# PowerSupply.net
KiCad netlist of a schematic drawn in Altium Designer
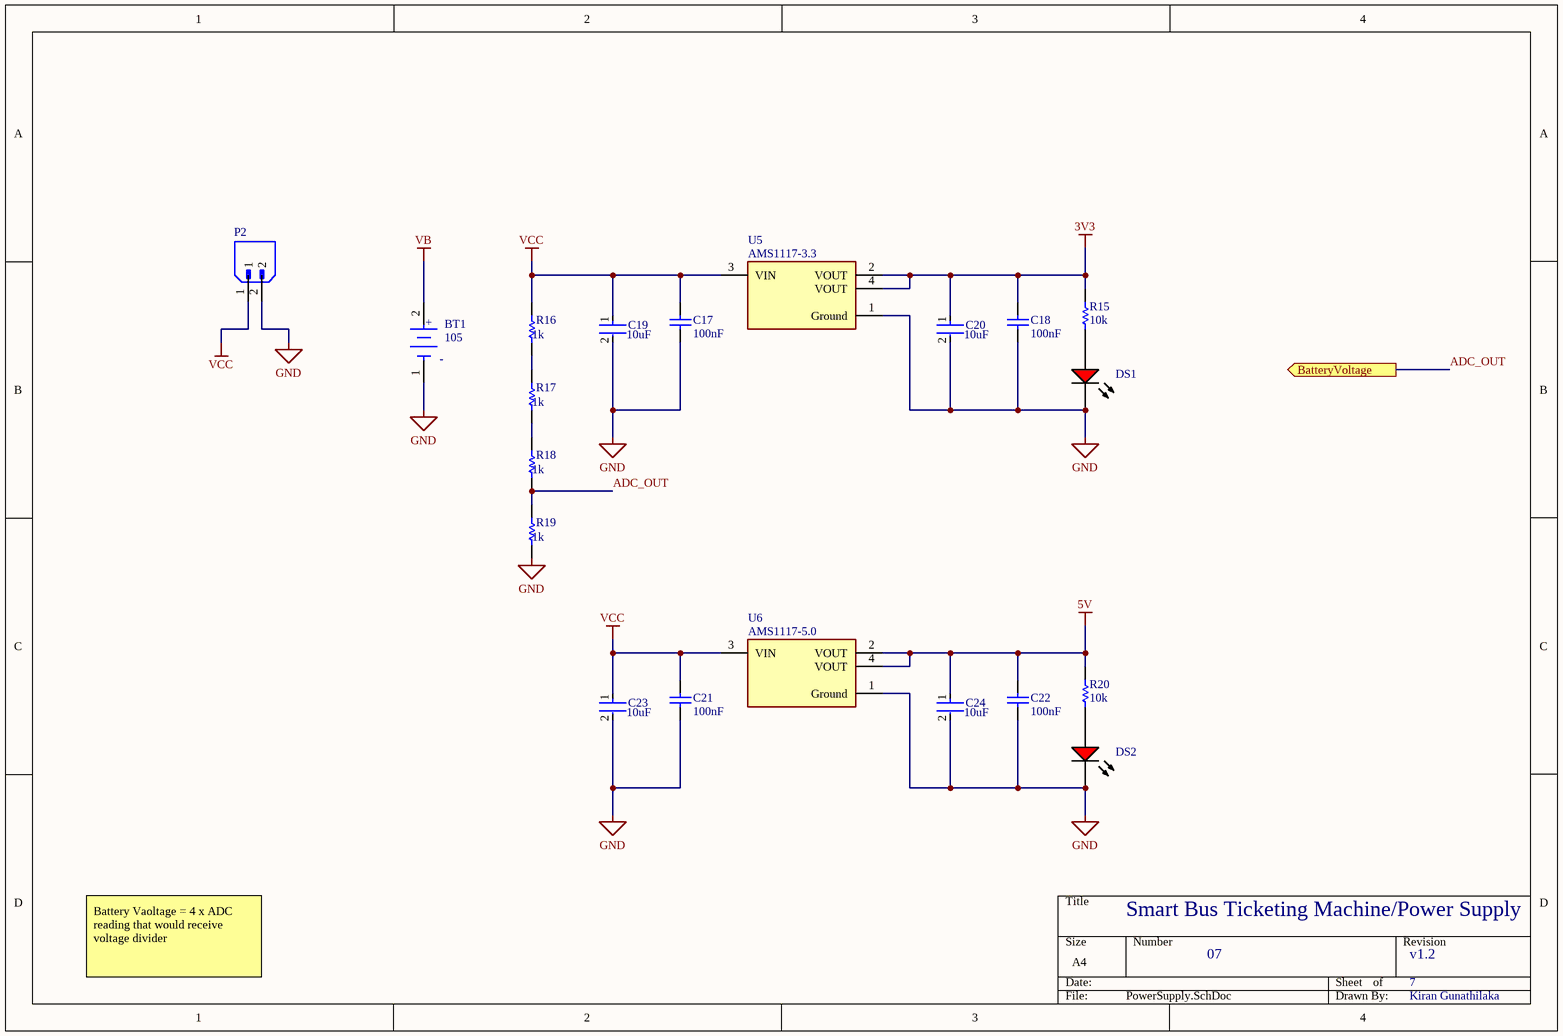
[diagram p0: PowerSupply.SchDoc]

(export (version "E")
  (design (tool "Eeschema 10.0.6"))
  (components
    (comp (ref "BT1")
      (value "105")
      (footprint "FP-105-MFG")
      (description "105 Battery Holder Coin Cell 1 Cell PC Pin PCB Through Hole Mount PBT 0.944 in. Dia")
      (libsource (lib "Altium Content Vault") (part "db879b5662d49c975a5ff8b5862d222"))
    )
    (comp (ref "C17")
      (value "100nF")
      (footprint "CAPC2013X94X50ML20T25")
      (fields
        (field (name "MANUFACTURER") "AVX Interconnect / Elco")
        (field (name "PART NUMBER") "08051C152KAT2A")
      )
      (libsource (lib "Altium Content Vault") (part "CAP"))
    )
    (comp (ref "C18")
      (value "100nF")
      (footprint "CAPC2013X94X50ML20T25")
      (fields
        (field (name "MANUFACTURER") "AVX Interconnect / Elco")
        (field (name "PART NUMBER") "08051C152KAT2A")
      )
      (libsource (lib "Altium Content Vault") (part "CAP"))
    )
    (comp (ref "C19")
      (value "C0805C106K9PACTU")
      (footprint "FP-C0805C106K9PACTU-MFG")
      (description "CAP CER 10UF 6.3V X5R 0805")
      (fields
        (field (name "CAPACITANCE") "10uF")
        (field (name "VOLTAGE") "6.3V")
        (field (name "TOLERANCE") "10%")
      )
      (libsource (lib "Altium Content Vault") (part "b4654b650e69147ec39a6b967a45e02"))
    )
    (comp (ref "C20")
      (value "C0805C106K9PACTU")
      (footprint "FP-C0805C106K9PACTU-MFG")
      (description "CAP CER 10UF 6.3V X5R 0805")
      (fields
        (field (name "CAPACITANCE") "10uF")
        (field (name "VOLTAGE") "6.3V")
        (field (name "TOLERANCE") "10%")
      )
      (libsource (lib "Altium Content Vault") (part "b4654b650e69147ec39a6b967a45e02"))
    )
    (comp (ref "C21")
      (value "100nF")
      (footprint "CAPC2013X94X50ML20T25")
      (fields
        (field (name "MANUFACTURER") "AVX Interconnect / Elco")
        (field (name "PART NUMBER") "08051C152KAT2A")
      )
      (libsource (lib "Altium Content Vault") (part "CAP"))
    )
    (comp (ref "C22")
      (value "100nF")
      (footprint "CAPC2013X94X50ML20T25")
      (fields
        (field (name "MANUFACTURER") "AVX Interconnect / Elco")
        (field (name "PART NUMBER") "08051C152KAT2A")
      )
      (libsource (lib "Altium Content Vault") (part "CAP"))
    )
    (comp (ref "C23")
      (value "C0805C106K9PACTU")
      (footprint "FP-C0805C106K9PACTU-MFG")
      (description "CAP CER 10UF 6.3V X5R 0805")
      (fields
        (field (name "CAPACITANCE") "10uF")
        (field (name "VOLTAGE") "6.3V")
        (field (name "TOLERANCE") "10%")
      )
      (libsource (lib "Altium Content Vault") (part "b4654b650e69147ec39a6b967a45e02"))
    )
    (comp (ref "C24")
      (value "C0805C106K9PACTU")
      (footprint "FP-C0805C106K9PACTU-MFG")
      (description "CAP CER 10UF 6.3V X5R 0805")
      (fields
        (field (name "CAPACITANCE") "10uF")
        (field (name "VOLTAGE") "6.3V")
        (field (name "TOLERANCE") "10%")
      )
      (libsource (lib "Altium Content Vault") (part "b4654b650e69147ec39a6b967a45e02"))
    )
    (comp (ref "DS1")
      (value "HSMH-C150")
      (footprint "AVAG-HSMX-C150_V")
      (description "LED Uni-Color Red, 65 mW, 25 mA, -40 to 85 degC, 2-Pin SMD, RoHS, Tape and Reel")
      (fields (field (name "MANUFACTURER") "Avago"))
      (libsource (lib "Altium Content Vault") (part "LED-RED-AK-2"))
    )
    (comp (ref "DS2")
      (value "HSMH-C150")
      (footprint "AVAG-HSMX-C150_V")
      (description "LED Uni-Color Red, 65 mW, 25 mA, -40 to 85 degC, 2-Pin SMD, RoHS, Tape and Reel")
      (fields (field (name "MANUFACTURER") "Avago"))
      (libsource (lib "Altium Content Vault") (part "LED-RED-AK-2"))
    )
    (comp (ref "P2")
      (value "Battery Connector")
      (footprint "JST_B2B-XH-A(LF)(SN)")
      (libsource (lib "SchemLib") (part "TX_RX Header"))
    )
    (comp (ref "R15")
      (value "10k")
      (footprint "RESC2013X60X35NL10T20")
      (description "Chip Resistor, 10 KOhm, +/- 1%, 0.125 W, -55 to 155 degC, 0805 (2012 Metric), RoHS, Tape and Reel")
      (fields (field (name "MANUFACTURER") "Yageo") (field (name "Comment") "RC0805FR-0710KL"))
      (libsource (lib "Altium Content Vault") (part "RES-2"))
    )
    (comp (ref "R16")
      (value "RC0805FR-071KL")
      (footprint "RESC2013X60X35ML10T20")
      (description "Chip Resistor, 1 KOhm, +/- 1%, 125 mW, -55 to 155 degC, 0805 (2012 Metric), RoHS, Tape and Reel")
      (fields
        (field (name "RESISTANCE") "1k")
        (field (name "TOLERANCE") "1%")
        (field (name "MANUFACTURER") "Yageo")
      )
      (libsource (lib "Altium Content Vault") (part "RES-2"))
    )
    (comp (ref "R17")
      (value "RC0805FR-071KL")
      (footprint "RESC2013X60X35ML10T20")
      (description "Chip Resistor, 1 KOhm, +/- 1%, 125 mW, -55 to 155 degC, 0805 (2012 Metric), RoHS, Tape and Reel")
      (fields
        (field (name "RESISTANCE") "1k")
        (field (name "TOLERANCE") "1%")
        (field (name "MANUFACTURER") "Yageo")
      )
      (libsource (lib "Altium Content Vault") (part "RES-2"))
    )
    (comp (ref "R18")
      (value "RC0805FR-071KL")
      (footprint "RESC2013X60X35ML10T20")
      (description "Chip Resistor, 1 KOhm, +/- 1%, 125 mW, -55 to 155 degC, 0805 (2012 Metric), RoHS, Tape and Reel")
      (fields
        (field (name "RESISTANCE") "1k")
        (field (name "TOLERANCE") "1%")
        (field (name "MANUFACTURER") "Yageo")
      )
      (libsource (lib "Altium Content Vault") (part "RES-2"))
    )
    (comp (ref "R19")
      (value "RC0805FR-071KL")
      (footprint "RESC2013X60X35ML10T20")
      (description "Chip Resistor, 1 KOhm, +/- 1%, 125 mW, -55 to 155 degC, 0805 (2012 Metric), RoHS, Tape and Reel")
      (fields
        (field (name "RESISTANCE") "1k")
        (field (name "TOLERANCE") "1%")
        (field (name "MANUFACTURER") "Yageo")
      )
      (libsource (lib "Altium Content Vault") (part "RES-2"))
    )
    (comp (ref "R20")
      (value "10k")
      (footprint "RESC2013X60X35NL10T20")
      (description "Chip Resistor, 10 KOhm, +/- 1%, 0.125 W, -55 to 155 degC, 0805 (2012 Metric), RoHS, Tape and Reel")
      (fields (field (name "MANUFACTURER") "Yageo") (field (name "Comment") "RC0805FR-0710KL"))
      (libsource (lib "Altium Content Vault") (part "RES-2"))
    )
    (comp (ref "U5")
      (value "AMS1117-3.3")
      (footprint "FP-AMS1117-IPC_C")
      (description "LDO Voltage Regulators 1A, 3.3V")
      (fields
        (field (name "OCTOPART") "https://octopart.com/ams1117-3.3-advanced+monolithic+systems-25899300")
        (field (name "MANUFACTURER") "Advanced Monolithic Systems")
      )
      (libsource (lib "Altium Content Vault") (part "8bdbb5f8e77002000e30dd2845d0354"))
    )
    (comp (ref "U6")
      (value "AMS1117-5.0")
      (footprint "FP-AMS1117-IPC_C")
      (description "LDO Voltage Regulators 1A, 3.3V")
      (fields
        (field (name "MANUFACTURER PART NUMBER") "AMS1117-3.3")
        (field (name "OCTOPART") "https://octopart.com/ams1117-3.3-advanced+monolithic+systems-25899300")
      )
      (libsource (lib "Altium Content Vault") (part "8bdbb5f8e77002000e30dd2845d0354"))
    )
  )
  (nets
    (net (code "1") (name "/ADC_OUT") (class "Default")
      (node (ref "R18") (pin "1") (pinfunction "1_1") (pintype "passive"))
      (node (ref "R19") (pin "2") (pinfunction "2_2") (pintype "passive"))
    )
    (net (code "2") (name "3V3") (class "Default")
      (node (ref "C18") (pin "2") (pinfunction "2_2") (pintype "passive"))
      (node (ref "C20") (pin "1") (pinfunction "1_1") (pintype "passive"))
      (node (ref "R15") (pin "1") (pinfunction "1_1") (pintype "passive"))
      (node (ref "U5") (pin "2") (pinfunction "VOUT_2") (pintype "passive"))
      (node (ref "U5") (pin "4") (pinfunction "VOUT_4") (pintype "passive"))
    )
    (net (code "3") (name "5V") (class "Default")
      (node (ref "C22") (pin "2") (pinfunction "2_2") (pintype "passive"))
      (node (ref "C24") (pin "1") (pinfunction "1_1") (pintype "passive"))
      (node (ref "R20") (pin "1") (pinfunction "1_1") (pintype "passive"))
      (node (ref "U6") (pin "2") (pinfunction "VOUT_2") (pintype "passive"))
      (node (ref "U6") (pin "4") (pinfunction "VOUT_4") (pintype "passive"))
    )
    (net (code "4") (name "GND") (class "Default")
      (node (ref "BT1") (pin "1") (pinfunction "-_1") (pintype "passive"))
      (node (ref "C17") (pin "1") (pinfunction "1_1") (pintype "passive"))
      (node (ref "C18") (pin "1") (pinfunction "1_1") (pintype "passive"))
      (node (ref "C19") (pin "2") (pinfunction "2_2") (pintype "passive"))
      (node (ref "C20") (pin "2") (pinfunction "2_2") (pintype "passive"))
      (node (ref "C21") (pin "1") (pinfunction "1_1") (pintype "passive"))
      (node (ref "C22") (pin "1") (pinfunction "1_1") (pintype "passive"))
      (node (ref "C23") (pin "2") (pinfunction "2_2") (pintype "passive"))
      (node (ref "C24") (pin "2") (pinfunction "2_2") (pintype "passive"))
      (node (ref "DS1") (pin "2") (pinfunction "K_2") (pintype "passive"))
      (node (ref "DS2") (pin "2") (pinfunction "K_2") (pintype "passive"))
      (node (ref "P2") (pin "2") (pinfunction "2_2") (pintype "passive"))
      (node (ref "R19") (pin "1") (pinfunction "1_1") (pintype "passive"))
      (node (ref "U5") (pin "1") (pinfunction "Ground_1") (pintype "passive"))
      (node (ref "U6") (pin "1") (pinfunction "Ground_1") (pintype "passive"))
    )
    (net (code "5") (name "Net-(DS1-A)") (class "Default")
      (node (ref "DS1") (pin "1") (pinfunction "A_1") (pintype "passive"))
      (node (ref "R15") (pin "2") (pinfunction "2_2") (pintype "passive"))
    )
    (net (code "6") (name "Net-(DS2-A)") (class "Default")
      (node (ref "DS2") (pin "1") (pinfunction "A_1") (pintype "passive"))
      (node (ref "R20") (pin "2") (pinfunction "2_2") (pintype "passive"))
    )
    (net (code "7") (name "Net-(R16-Pad1)") (class "Default")
      (node (ref "R16") (pin "1") (pinfunction "1_1") (pintype "passive"))
      (node (ref "R17") (pin "2") (pinfunction "2_2") (pintype "passive"))
    )
    (net (code "8") (name "Net-(R17-Pad1)") (class "Default")
      (node (ref "R17") (pin "1") (pinfunction "1_1") (pintype "passive"))
      (node (ref "R18") (pin "2") (pinfunction "2_2") (pintype "passive"))
    )
    (net (code "9") (name "VB") (class "Default")
      (node (ref "BT1") (pin "2") (pinfunction "+_2") (pintype "passive"))
    )
    (net (code "10") (name "VCC") (class "Default")
      (node (ref "C17") (pin "2") (pinfunction "2_2") (pintype "passive"))
      (node (ref "C19") (pin "1") (pinfunction "1_1") (pintype "passive"))
      (node (ref "C21") (pin "2") (pinfunction "2_2") (pintype "passive"))
      (node (ref "C23") (pin "1") (pinfunction "1_1") (pintype "passive"))
      (node (ref "P2") (pin "1") (pinfunction "1_1") (pintype "passive"))
      (node (ref "R16") (pin "2") (pinfunction "2_2") (pintype "passive"))
      (node (ref "U5") (pin "3") (pinfunction "VIN_3") (pintype "passive"))
      (node (ref "U6") (pin "3") (pinfunction "VIN_3") (pintype "passive"))
    )
  )
)
